# ZYNQ_CONFIG.net
KiCad netlist of a schematic drawn in Altium Designer
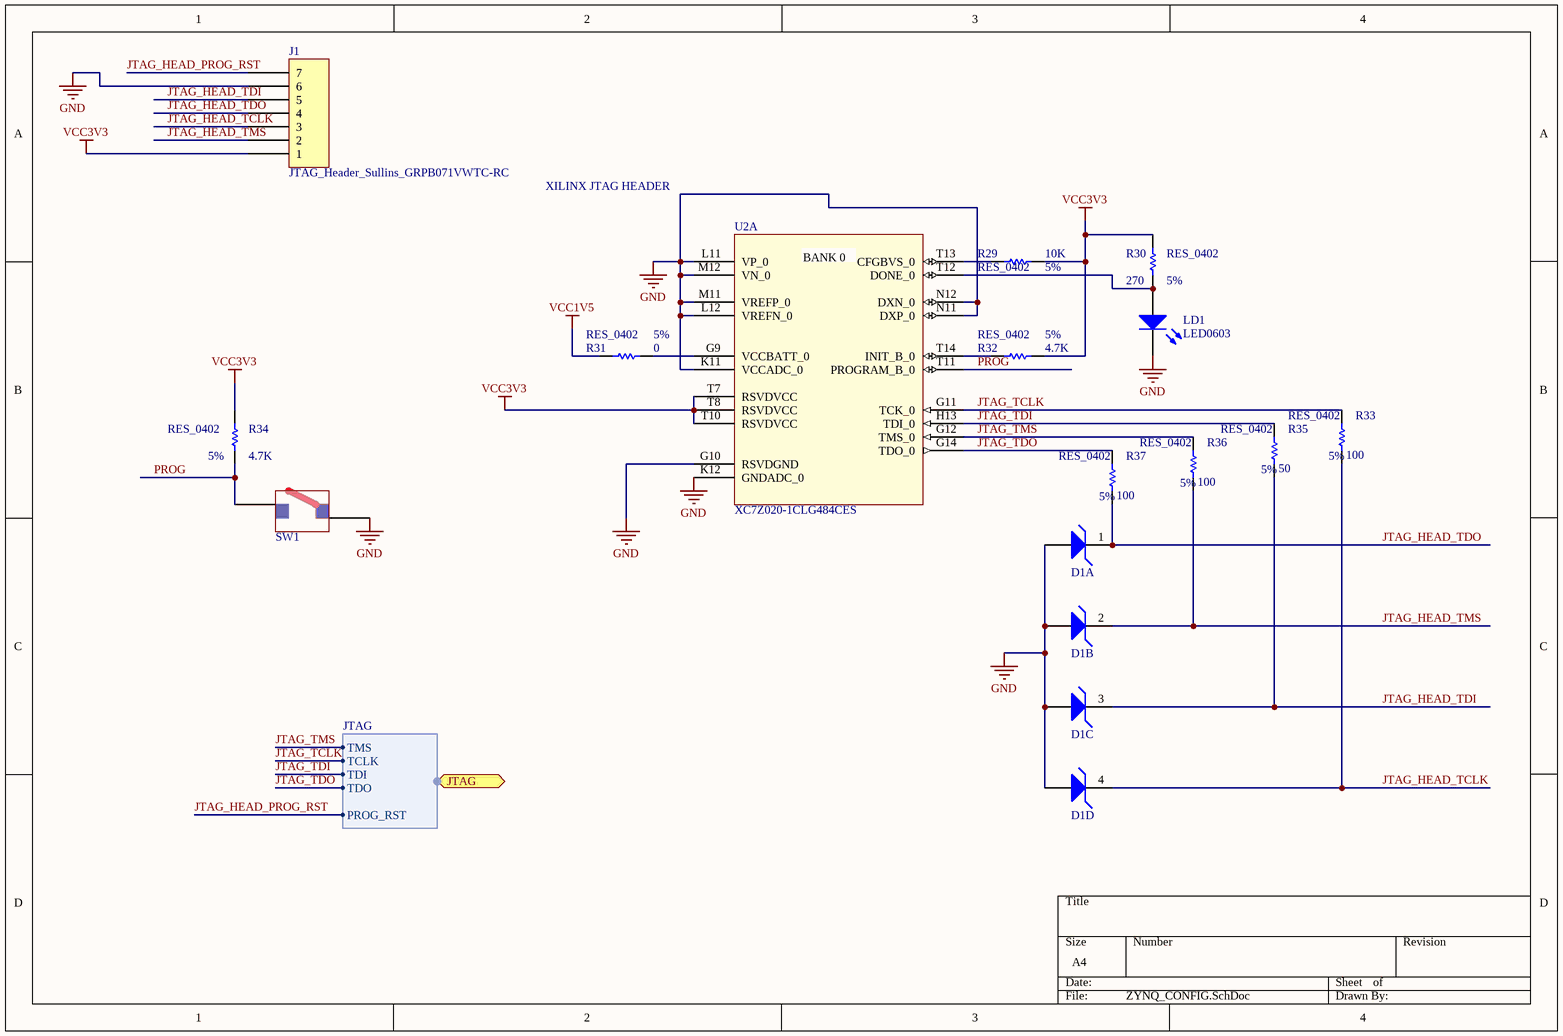
[diagram p0: ZYNQ_CONFIG.SchDoc]

(export (version "E")
  (design (tool "Eeschema 10.0.6"))
  (components
    (comp (ref "D1")
      (value "QuadESDDiode_TEConnectivity_SESD0802Q4UG")
      (footprint "QuadESDDiode_TEConnectivity_SESD0802Q4UG_5-PIN")
      (description "SESD0802Q4UG, Quad Diode Array for ESD protection")
      (fields (field (name "PART NUMBER") "RF2197-000") (field (name "MANUFACTURER") "TE Connectivity"))
      (libsource (lib "COMRAD_Database") (part "QuadESDDiode_TEConnectivity_SESD0802Q4UG"))
    )
    (comp (ref "J1")
      (value "JTAG_Header_Sullins_GRPB071VWTC-RC")
      (footprint "JTAG_Header_Sullins_GRPB071VWTC-RC_7-Pos")
      (description "CONN HEADER .050\" 7POS SMD GOLD")
      (fields
        (field (name "PART NUMBER") "GRPB071VWTC-RC")
        (field (name "MANUFACTURER") "Sullins Connector Solutions")
      )
      (libsource (lib "COMRAD_Database") (part "JTAG_Header_Sullins_GRPB071VWTC-RC"))
    )
    (comp (ref "LD1")
      (value "LED0603")
      (footprint "LED0603(1608):LED0603(1608)")
      (description "LED 565NM GRN DIFF 0603 SMD")
      (fields
        (field (name "PART NUMBER") "SML-LX0603GW-TR")
        (field (name "MANUFACTURER") "Lumex Opto/Components Inc")
      )
      (libsource (lib "COMRAD_Database") (part "LED0603"))
    )
    (comp (ref "R29")
      (value "RES_0402")
      (footprint "RESC0402(1005)_N:RESC0402(1005)_N")
      (description "10K ohm, 5%, 1/16W, 0402")
      (fields
        (field (name "ALTIUM_VALUE") "10K")
        (field (name "TOLERANCE") "5%")
        (field (name "PART NUMBER") "RC0402JR-0710KL")
        (field (name "MANUFACTURER") "Yageo America")
      )
      (libsource (lib "COMRAD_Database") (part "RES_0402"))
    )
    (comp (ref "R30")
      (value "RES_0402")
      (footprint "RESC0402(1005)_N:RESC0402(1005)_N")
      (description "270 ohm, 5%, 1/16W, 0402")
      (fields
        (field (name "ALTIUM_VALUE") "270")
        (field (name "TOLERANCE") "5%")
        (field (name "PART NUMBER") "RC0402JR-07270RL")
        (field (name "MANUFACTURER") "Yageo America")
      )
      (libsource (lib "COMRAD_Database") (part "RES_0402"))
    )
    (comp (ref "R31")
      (value "RES_0402")
      (footprint "RESC0402(1005)_N:RESC0402(1005)_N")
      (description "0.0 ohm shunt, 5%, 1/16W, 0402")
      (fields
        (field (name "ALTIUM_VALUE") "0")
        (field (name "TOLERANCE") "5%")
        (field (name "PART NUMBER") "RC0402JR-070RL")
        (field (name "MANUFACTURER") "Yageo America")
      )
      (libsource (lib "COMRAD_Database") (part "RES_0402"))
    )
    (comp (ref "R32")
      (value "RES_0402")
      (footprint "RESC0402(1005)_N:RESC0402(1005)_N")
      (description "4.7K ohm, 5%, 1/16W, 0402")
      (fields
        (field (name "ALTIUM_VALUE") "4.7K")
        (field (name "TOLERANCE") "5%")
        (field (name "PART NUMBER") "RC0402JR-074K7L")
        (field (name "MANUFACTURER") "Yageo America")
      )
      (libsource (lib "COMRAD_Database") (part "RES_0402"))
    )
    (comp (ref "R33")
      (value "RES_0402")
      (footprint "RESC0402(1005)_N:RESC0402(1005)_N")
      (description "100 ohm, 5%, 1/16W, 0402")
      (fields
        (field (name "ALTIUM_VALUE") "100")
        (field (name "TOLERANCE") "5%")
        (field (name "PART NUMBER") "RC0402JR-07100RL")
        (field (name "MANUFACTURER") "Yageo America")
      )
      (libsource (lib "COMRAD_Database") (part "RES_0402"))
    )
    (comp (ref "R34")
      (value "RES_0402")
      (footprint "RESC0402(1005)_N:RESC0402(1005)_N")
      (description "4.7K ohm, 5%, 1/16W, 0402")
      (fields
        (field (name "ALTIUM_VALUE") "4.7K")
        (field (name "TOLERANCE") "5%")
        (field (name "PART NUMBER") "RC0402JR-074K7L")
        (field (name "MANUFACTURER") "Yageo America")
      )
      (libsource (lib "COMRAD_Database") (part "RES_0402"))
    )
    (comp (ref "R35")
      (value "RES_0402")
      (footprint "RESC0402(1005)_N:RESC0402(1005)_N")
      (description "50 ohm, 5% 50mW, 0402")
      (fields
        (field (name "ALTIUM_VALUE") "50")
        (field (name "TOLERANCE") "5%")
        (field (name "PART NUMBER") "FC0402E50R0JTBST1")
        (field (name "MANUFACTURER") "VISHAY SILICONIX")
      )
      (libsource (lib "COMRAD_Database") (part "RES_0402"))
    )
    (comp (ref "R36")
      (value "RES_0402")
      (footprint "RESC0402(1005)_N:RESC0402(1005)_N")
      (description "100 ohm, 5%, 1/16W, 0402")
      (fields
        (field (name "ALTIUM_VALUE") "100")
        (field (name "TOLERANCE") "5%")
        (field (name "PART NUMBER") "RC0402JR-07100RL")
        (field (name "MANUFACTURER") "Yageo America")
      )
      (libsource (lib "COMRAD_Database") (part "RES_0402"))
    )
    (comp (ref "R37")
      (value "RES_0402")
      (footprint "RESC0402(1005)_N:RESC0402(1005)_N")
      (description "100 ohm, 5%, 1/16W, 0402")
      (fields
        (field (name "ALTIUM_VALUE") "100")
        (field (name "TOLERANCE") "5%")
        (field (name "PART NUMBER") "RC0402JR-07100RL")
        (field (name "MANUFACTURER") "Yageo America")
      )
      (libsource (lib "COMRAD_Database") (part "RES_0402"))
    )
    (comp (ref "SW1")
      (value "CHS-01TB")
      (footprint "DIP_Switch_SPST_CopalElectronics_CHS-01TB")
      (description "SWITCH DIP 1-POS SLIDE SMD")
      (fields (field (name "MANUFACTURER") "Copal Electronics Inc"))
      (libsource (lib "COMRAD_Database") (part "Switch"))
    )
    (comp (ref "U2")
      (value "XC7Z020-1CLG484CES")
      (footprint "ZYNQ_xc7z020clg484pkg_BGA-484")
      (description "XC7Z020-1CLG484CES, Zynq-7000 All Programmable SoC")
      (fields (field (name "MANUFACTURER") "Xilinx"))
      (libsource (lib "COMRAD_Database") (part "ZYNQ_XC7Z020CLG484PKG"))
    )
  )
  (nets
    (net (code "2") (name "/JTAG_HEAD_PROG_RST") (class "Default")
      (node (ref "J1") (pin "7") (pinfunction "7_7") (pintype "passive"))
    )
    (net (code "3") (name "/JTAG_HEAD_TCLK") (class "Default")
      (node (ref "D1") (pin "4") (pinfunction "K_4") (pintype "passive"))
      (node (ref "J1") (pin "3") (pinfunction "3_3") (pintype "passive"))
      (node (ref "R33") (pin "1") (pinfunction "1_1") (pintype "passive"))
    )
    (net (code "4") (name "/JTAG_HEAD_TDI") (class "Default")
      (node (ref "D1") (pin "3") (pinfunction "K_3") (pintype "passive"))
      (node (ref "J1") (pin "5") (pinfunction "5_5") (pintype "passive"))
      (node (ref "R35") (pin "1") (pinfunction "1_1") (pintype "passive"))
    )
    (net (code "5") (name "/JTAG_HEAD_TDO") (class "Default")
      (node (ref "D1") (pin "1") (pinfunction "K_1") (pintype "passive"))
      (node (ref "J1") (pin "4") (pinfunction "4_4") (pintype "passive"))
      (node (ref "R37") (pin "1") (pinfunction "1_1") (pintype "passive"))
    )
    (net (code "6") (name "/JTAG_HEAD_TMS") (class "Default")
      (node (ref "D1") (pin "2") (pinfunction "K_2") (pintype "passive"))
      (node (ref "J1") (pin "2") (pinfunction "2_2") (pintype "passive"))
      (node (ref "R36") (pin "1") (pinfunction "1_1") (pintype "passive"))
    )
    (net (code "7") (name "/JTAG_TCLK") (class "Default")
      (node (ref "R33") (pin "2") (pinfunction "2_2") (pintype "passive"))
      (node (ref "U2") (pin "G11") (pinfunction "TCK_0_G11") (pintype "input"))
    )
    (net (code "8") (name "/JTAG_TDI") (class "Default")
      (node (ref "R35") (pin "2") (pinfunction "2_2") (pintype "passive"))
      (node (ref "U2") (pin "H13") (pinfunction "TDI_0_H13") (pintype "input"))
    )
    (net (code "9") (name "/JTAG_TDO") (class "Default")
      (node (ref "R37") (pin "2") (pinfunction "2_2") (pintype "passive"))
      (node (ref "U2") (pin "G14") (pinfunction "TDO_0_G14") (pintype "output"))
    )
    (net (code "10") (name "/JTAG_TMS") (class "Default")
      (node (ref "R36") (pin "2") (pinfunction "2_2") (pintype "passive"))
      (node (ref "U2") (pin "G12") (pinfunction "TMS_0_G12") (pintype "input"))
    )
    (net (code "11") (name "/PROG") (class "Default")
      (node (ref "R34") (pin "1") (pinfunction "1_1") (pintype "passive"))
      (node (ref "SW1") (pin "1") (pintype "passive"))
      (node (ref "U2") (pin "T11") (pinfunction "PROGRAM_B_0_T11") (pintype "bidirectional"))
    )
    (net (code "13") (name "GND") (class "Default")
      (node (ref "D1") (pin "G") (pinfunction "A_G") (pintype "passive"))
      (node (ref "J1") (pin "6") (pinfunction "6_6") (pintype "passive"))
      (node (ref "LD1") (pin "1") (pinfunction "K_1") (pintype "passive"))
      (node (ref "SW1") (pin "2") (pintype "passive"))
      (node (ref "U2") (pin "G10") (pinfunction "RSVDGND_G10") (pintype "power_in"))
      (node (ref "U2") (pin "K11") (pinfunction "VCCADC_0_K11") (pintype "power_in"))
      (node (ref "U2") (pin "K12") (pinfunction "GNDADC_0_K12") (pintype "power_in"))
      (node (ref "U2") (pin "L11") (pinfunction "VP_0_L11") (pintype "power_in"))
      (node (ref "U2") (pin "L12") (pinfunction "VREFN_0_L12") (pintype "power_in"))
      (node (ref "U2") (pin "M11") (pinfunction "VREFP_0_M11") (pintype "power_in"))
      (node (ref "U2") (pin "M12") (pinfunction "VN_0_M12") (pintype "power_in"))
      (node (ref "U2") (pin "N11") (pinfunction "DXP_0_N11") (pintype "bidirectional"))
      (node (ref "U2") (pin "N12") (pinfunction "DXN_0_N12") (pintype "bidirectional"))
    )
    (net (code "14") (name "Net-(LD1-A)") (class "Default")
      (node (ref "LD1") (pin "2") (pinfunction "A_2") (pintype "passive"))
      (node (ref "R30") (pin "1") (pinfunction "1_1") (pintype "passive"))
      (node (ref "U2") (pin "T12") (pinfunction "DONE_0_T12") (pintype "bidirectional"))
    )
    (net (code "15") (name "Net-(U2A-CFGBVS_0)") (class "Default")
      (node (ref "R29") (pin "1") (pinfunction "1_1") (pintype "passive"))
      (node (ref "U2") (pin "T13") (pinfunction "CFGBVS_0_T13") (pintype "bidirectional"))
    )
    (net (code "16") (name "Net-(U2A-INIT_B_0)") (class "Default")
      (node (ref "R32") (pin "1") (pinfunction "1_1") (pintype "passive"))
      (node (ref "U2") (pin "T14") (pinfunction "INIT_B_0_T14") (pintype "bidirectional"))
    )
    (net (code "17") (name "Net-(U2A-VCCBATT_0)") (class "Default")
      (node (ref "R31") (pin "2") (pinfunction "2_2") (pintype "passive"))
      (node (ref "U2") (pin "G9") (pinfunction "VCCBATT_0_G9") (pintype "power_in"))
    )
    (net (code "18") (name "VCC1V5") (class "Default")
      (node (ref "R31") (pin "1") (pinfunction "1_1") (pintype "passive"))
    )
    (net (code "19") (name "VCC3V3") (class "Default")
      (node (ref "J1") (pin "1") (pinfunction "1_1") (pintype "passive"))
      (node (ref "R29") (pin "2") (pinfunction "2_2") (pintype "passive"))
      (node (ref "R30") (pin "2") (pinfunction "2_2") (pintype "passive"))
      (node (ref "R32") (pin "2") (pinfunction "2_2") (pintype "passive"))
      (node (ref "R34") (pin "2") (pinfunction "2_2") (pintype "passive"))
      (node (ref "U2") (pin "T10") (pinfunction "RSVDVCC_T10") (pintype "power_in"))
      (node (ref "U2") (pin "T7") (pinfunction "RSVDVCC_T7") (pintype "power_in"))
      (node (ref "U2") (pin "T8") (pinfunction "RSVDVCC_T8") (pintype "power_in"))
    )
  )
)
